# pc-gen-usb-fixgain.net
KiCad netlist of a schematic drawn in EAGLE
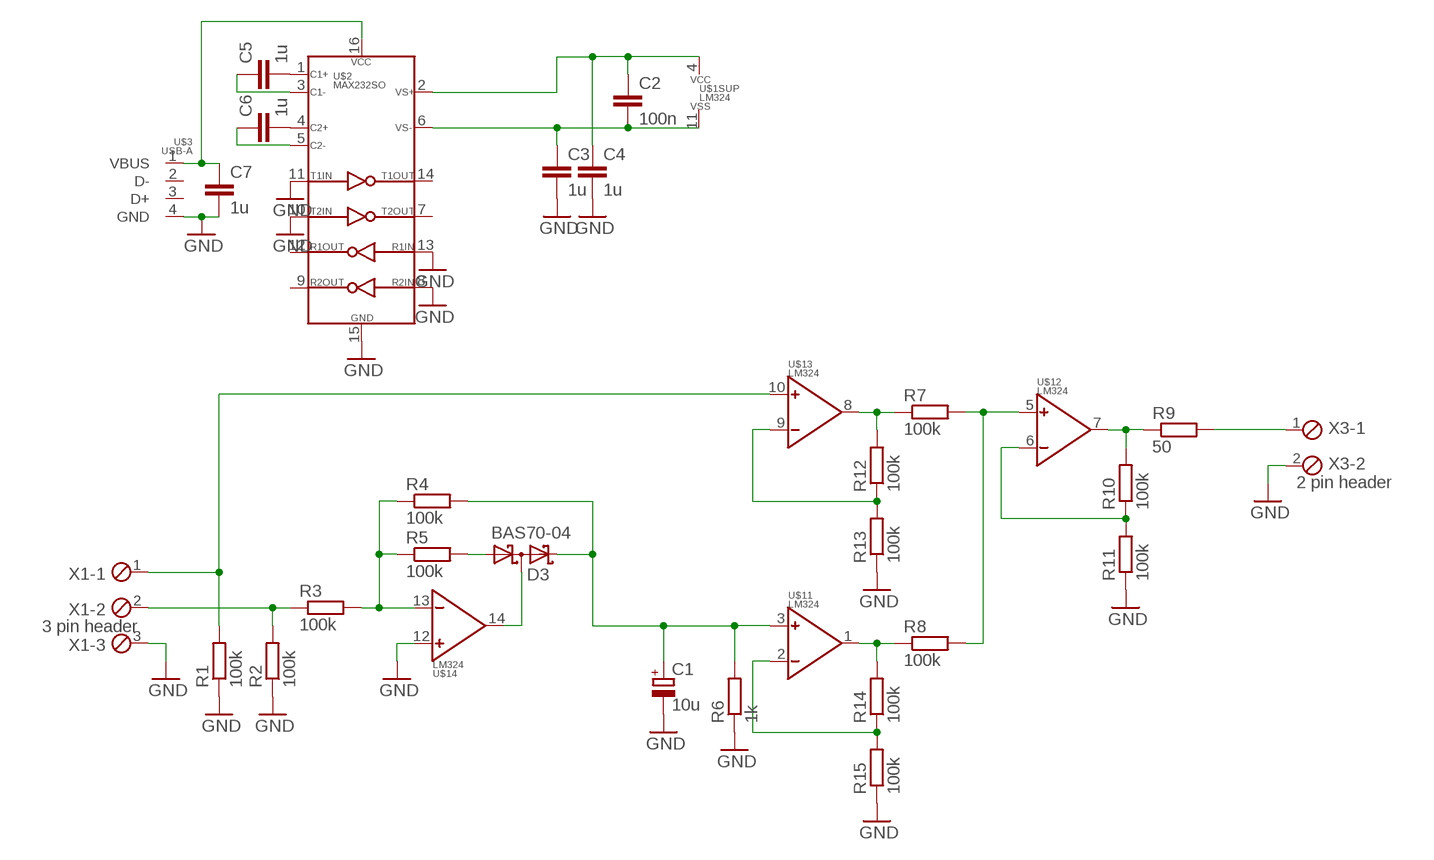
[diagram p0: schematic, sheet 1]

(export (version "E")
  (design (tool "Eeschema 10.0.6"))
  (components
    (comp (ref "C1")
      (value "10u")
      (footprint "eagle-import:E2,5-7")
      (libsource (lib "eagle-import") (part "CPOL-EUE2.5-7"))
    )
    (comp (ref "C2")
      (value "100n")
      (footprint "eagle-import:C1206")
      (libsource (lib "eagle-import") (part "C-EUC1206"))
    )
    (comp (ref "C3")
      (value "1u")
      (footprint "eagle-import:C1206")
      (libsource (lib "eagle-import") (part "C-EUC1206"))
    )
    (comp (ref "C4")
      (value "1u")
      (footprint "eagle-import:C1206")
      (libsource (lib "eagle-import") (part "C-EUC1206"))
    )
    (comp (ref "C5")
      (value "1u")
      (footprint "eagle-import:C1206")
      (libsource (lib "eagle-import") (part "C-EUC1206"))
    )
    (comp (ref "C6")
      (value "1u")
      (footprint "eagle-import:C1206")
      (libsource (lib "eagle-import") (part "C-EUC1206"))
    )
    (comp (ref "C7")
      (value "1u")
      (footprint "eagle-import:C1206")
      (libsource (lib "eagle-import") (part "C-EUC1206"))
    )
    (comp (ref "D3")
      (value "BAS70-04")
      (footprint "eagle-import:SOT23")
      (libsource (lib "eagle-import") (part "BAS70-04"))
    )
    (comp (ref "R1")
      (value "100k")
      (footprint "eagle-import:R1206")
      (libsource (lib "eagle-import") (part "R-EU_R1206"))
    )
    (comp (ref "R2")
      (value "100k")
      (footprint "eagle-import:R1206")
      (libsource (lib "eagle-import") (part "R-EU_R1206"))
    )
    (comp (ref "R3")
      (value "100k")
      (footprint "eagle-import:R1206")
      (libsource (lib "eagle-import") (part "R-EU_R1206"))
    )
    (comp (ref "R4")
      (value "100k")
      (footprint "eagle-import:R1206")
      (libsource (lib "eagle-import") (part "R-EU_R1206"))
    )
    (comp (ref "R5")
      (value "100k")
      (footprint "eagle-import:R1206")
      (libsource (lib "eagle-import") (part "R-EU_R1206"))
    )
    (comp (ref "R6")
      (value "1k")
      (footprint "eagle-import:R1206")
      (libsource (lib "eagle-import") (part "R-EU_R1206"))
    )
    (comp (ref "R7")
      (value "100k")
      (footprint "eagle-import:R1206")
      (libsource (lib "eagle-import") (part "R-EU_R1206"))
    )
    (comp (ref "R8")
      (value "100k")
      (footprint "eagle-import:R1206")
      (libsource (lib "eagle-import") (part "R-EU_R1206"))
    )
    (comp (ref "R9")
      (value "50")
      (footprint "eagle-import:R1206")
      (libsource (lib "eagle-import") (part "R-EU_R1206"))
    )
    (comp (ref "R10")
      (value "100k")
      (footprint "eagle-import:R1206")
      (libsource (lib "eagle-import") (part "R-EU_R1206"))
    )
    (comp (ref "R11")
      (value "100k")
      (footprint "eagle-import:R1206")
      (libsource (lib "eagle-import") (part "R-EU_R1206"))
    )
    (comp (ref "R12")
      (value "100k")
      (footprint "eagle-import:R1206")
      (libsource (lib "eagle-import") (part "R-EU_R1206"))
    )
    (comp (ref "R13")
      (value "100k")
      (footprint "eagle-import:R1206")
      (libsource (lib "eagle-import") (part "R-EU_R1206"))
    )
    (comp (ref "R14")
      (value "100k")
      (footprint "eagle-import:R1206")
      (libsource (lib "eagle-import") (part "R-EU_R1206"))
    )
    (comp (ref "R15")
      (value "100k")
      (footprint "eagle-import:R1206")
      (libsource (lib "eagle-import") (part "R-EU_R1206"))
    )
    (comp (ref "U$1")
      (value "LM324")
      (footprint "eagle-import:SO14")
      (libsource (lib "eagle-import") (part "OP-QUADSO14"))
    )
    (comp (ref "U$2")
      (value "MAX232SO")
      (footprint "eagle-import:SO16")
      (libsource (lib "eagle-import") (part "MAX232SO"))
    )
    (comp (ref "U$3")
      (value "USB-A")
      (footprint "eagle-import:USB-A")
      (libsource (lib "eagle-import") (part "USB-A"))
    )
    (comp (ref "X1")
      (value "3 pin header")
      (footprint "eagle-import:3POL254")
      (libsource (lib "eagle-import") (part "MPT3"))
    )
    (comp (ref "X3")
      (value "2 pin header")
      (footprint "eagle-import:2POL254")
      (libsource (lib "eagle-import") (part "MPT2"))
    )
  )
  (nets
    (net (code "1") (name "GND") (class "Default")
      (node (ref "C1") (pin "-") (pinfunction "-_-") (pintype "passive"))
      (node (ref "C3") (pin "2") (pinfunction "2_2") (pintype "passive"))
      (node (ref "C4") (pin "2") (pinfunction "2_2") (pintype "passive"))
      (node (ref "C7") (pin "2") (pinfunction "2_2") (pintype "passive"))
      (node (ref "R1") (pin "1") (pinfunction "1_1") (pintype "passive"))
      (node (ref "R11") (pin "1") (pinfunction "1_1") (pintype "passive"))
      (node (ref "R13") (pin "1") (pinfunction "1_1") (pintype "passive"))
      (node (ref "R15") (pin "1") (pinfunction "1_1") (pintype "passive"))
      (node (ref "R2") (pin "1") (pinfunction "1_1") (pintype "passive"))
      (node (ref "R6") (pin "1") (pinfunction "1_1") (pintype "passive"))
      (node (ref "U$1") (pin "12") (pinfunction "POS_12") (pintype "bidirectional"))
      (node (ref "U$2") (pin "10") (pinfunction "T2IN_10") (pintype "bidirectional"))
      (node (ref "U$2") (pin "11") (pinfunction "T1IN_11") (pintype "bidirectional"))
      (node (ref "U$2") (pin "13") (pinfunction "R1IN_13") (pintype "bidirectional"))
      (node (ref "U$2") (pin "15") (pinfunction "GND_15") (pintype "bidirectional"))
      (node (ref "U$2") (pin "8") (pinfunction "R2IN_8") (pintype "bidirectional"))
      (node (ref "U$3") (pin "4") (pinfunction "GND_4") (pintype "bidirectional"))
      (node (ref "X1") (pin "3") (pinfunction "1_3") (pintype "passive"))
      (node (ref "X3") (pin "2") (pinfunction "1_2") (pintype "passive"))
    )
    (net (code "2") (name "Net-(D3-A1)") (class "Default")
      (node (ref "D3") (pin "1") (pinfunction "A1_1") (pintype "passive"))
      (node (ref "R5") (pin "2") (pinfunction "2_2") (pintype "passive"))
    )
    (net (code "3") (name "Net-(D3-C1A2)") (class "Default")
      (node (ref "D3") (pin "3") (pinfunction "C1A2_3") (pintype "passive"))
      (node (ref "U$1") (pin "14") (pinfunction "OUT_14") (pintype "bidirectional"))
    )
    (net (code "4") (name "Net-(D3-C2)") (class "Default")
      (node (ref "C1") (pin "+") (pinfunction "+_+") (pintype "passive"))
      (node (ref "D3") (pin "2") (pinfunction "C2_2") (pintype "passive"))
      (node (ref "R4") (pin "2") (pinfunction "2_2") (pintype "passive"))
      (node (ref "R6") (pin "2") (pinfunction "2_2") (pintype "passive"))
      (node (ref "U$1") (pin "3") (pinfunction "POS_3") (pintype "bidirectional"))
    )
    (net (code "5") (name "Net-(R9-Pad2)") (class "Default")
      (node (ref "R9") (pin "2") (pinfunction "2_2") (pintype "passive"))
      (node (ref "X3") (pin "1") (pinfunction "1_1") (pintype "passive"))
    )
    (net (code "6") (name "Net-(U$1A-NEG)") (class "Default")
      (node (ref "R14") (pin "1") (pinfunction "1_1") (pintype "passive"))
      (node (ref "R15") (pin "2") (pinfunction "2_2") (pintype "passive"))
      (node (ref "U$1") (pin "2") (pinfunction "NEG_2") (pintype "bidirectional"))
    )
    (net (code "7") (name "Net-(U$1A-OUT)") (class "Default")
      (node (ref "R14") (pin "2") (pinfunction "2_2") (pintype "passive"))
      (node (ref "R8") (pin "1") (pinfunction "1_1") (pintype "passive"))
      (node (ref "U$1") (pin "1") (pinfunction "OUT_1") (pintype "bidirectional"))
    )
    (net (code "8") (name "Net-(U$1B-NEG)") (class "Default")
      (node (ref "R10") (pin "1") (pinfunction "1_1") (pintype "passive"))
      (node (ref "R11") (pin "2") (pinfunction "2_2") (pintype "passive"))
      (node (ref "U$1") (pin "6") (pinfunction "NEG_6") (pintype "bidirectional"))
    )
    (net (code "9") (name "Net-(U$1B-OUT)") (class "Default")
      (node (ref "R10") (pin "2") (pinfunction "2_2") (pintype "passive"))
      (node (ref "R9") (pin "1") (pinfunction "1_1") (pintype "passive"))
      (node (ref "U$1") (pin "7") (pinfunction "OUT_7") (pintype "bidirectional"))
    )
    (net (code "10") (name "Net-(U$1B-POS)") (class "Default")
      (node (ref "R7") (pin "2") (pinfunction "2_2") (pintype "passive"))
      (node (ref "R8") (pin "2") (pinfunction "2_2") (pintype "passive"))
      (node (ref "U$1") (pin "5") (pinfunction "POS_5") (pintype "bidirectional"))
    )
    (net (code "11") (name "Net-(U$1C-NEG)") (class "Default")
      (node (ref "R12") (pin "1") (pinfunction "1_1") (pintype "passive"))
      (node (ref "R13") (pin "2") (pinfunction "2_2") (pintype "passive"))
      (node (ref "U$1") (pin "9") (pinfunction "NEG_9") (pintype "bidirectional"))
    )
    (net (code "12") (name "Net-(U$1C-OUT)") (class "Default")
      (node (ref "R12") (pin "2") (pinfunction "2_2") (pintype "passive"))
      (node (ref "R7") (pin "1") (pinfunction "1_1") (pintype "passive"))
      (node (ref "U$1") (pin "8") (pinfunction "OUT_8") (pintype "bidirectional"))
    )
    (net (code "13") (name "Net-(U$1C-POS)") (class "Default")
      (node (ref "R1") (pin "2") (pinfunction "2_2") (pintype "passive"))
      (node (ref "U$1") (pin "10") (pinfunction "POS_10") (pintype "bidirectional"))
      (node (ref "X1") (pin "1") (pinfunction "1_1") (pintype "passive"))
    )
    (net (code "14") (name "Net-(U$1D-NEG)") (class "Default")
      (node (ref "R3") (pin "2") (pinfunction "2_2") (pintype "passive"))
      (node (ref "R4") (pin "1") (pinfunction "1_1") (pintype "passive"))
      (node (ref "R5") (pin "1") (pinfunction "1_1") (pintype "passive"))
      (node (ref "U$1") (pin "13") (pinfunction "NEG_13") (pintype "bidirectional"))
    )
    (net (code "15") (name "Net-(U$1E-VCC)") (class "Default")
      (node (ref "C2") (pin "1") (pinfunction "1_1") (pintype "passive"))
      (node (ref "C4") (pin "1") (pinfunction "1_1") (pintype "passive"))
      (node (ref "U$1") (pin "4") (pinfunction "VCC_4") (pintype "bidirectional"))
      (node (ref "U$2") (pin "2") (pinfunction "VS+_2") (pintype "bidirectional"))
    )
    (net (code "16") (name "Net-(U$1E-VSS)") (class "Default")
      (node (ref "C2") (pin "2") (pinfunction "2_2") (pintype "passive"))
      (node (ref "C3") (pin "1") (pinfunction "1_1") (pintype "passive"))
      (node (ref "U$1") (pin "11") (pinfunction "VSS_11") (pintype "bidirectional"))
      (node (ref "U$2") (pin "6") (pinfunction "VS-_6") (pintype "bidirectional"))
    )
    (net (code "17") (name "Net-(U$2-C1+)") (class "Default")
      (node (ref "C5") (pin "2") (pinfunction "2_2") (pintype "passive"))
      (node (ref "U$2") (pin "1") (pinfunction "C1+_1") (pintype "bidirectional"))
    )
    (net (code "18") (name "Net-(U$2-C1-)") (class "Default")
      (node (ref "C5") (pin "1") (pinfunction "1_1") (pintype "passive"))
      (node (ref "U$2") (pin "3") (pinfunction "C1-_3") (pintype "bidirectional"))
    )
    (net (code "19") (name "Net-(U$2-C2+)") (class "Default")
      (node (ref "C6") (pin "2") (pinfunction "2_2") (pintype "passive"))
      (node (ref "U$2") (pin "4") (pinfunction "C2+_4") (pintype "bidirectional"))
    )
    (net (code "20") (name "Net-(U$2-C2-)") (class "Default")
      (node (ref "C6") (pin "1") (pinfunction "1_1") (pintype "passive"))
      (node (ref "U$2") (pin "5") (pinfunction "C2-_5") (pintype "bidirectional"))
    )
    (net (code "21") (name "Net-(U$2-VCC)") (class "Default")
      (node (ref "C7") (pin "1") (pinfunction "1_1") (pintype "passive"))
      (node (ref "U$2") (pin "16") (pinfunction "VCC_16") (pintype "bidirectional"))
      (node (ref "U$3") (pin "1") (pinfunction "VBUS_1") (pintype "bidirectional"))
    )
    (net (code "22") (name "Net-(X1B-1)") (class "Default")
      (node (ref "R2") (pin "2") (pinfunction "2_2") (pintype "passive"))
      (node (ref "R3") (pin "1") (pinfunction "1_1") (pintype "passive"))
      (node (ref "X1") (pin "2") (pinfunction "1_2") (pintype "passive"))
    )
    (net (code "23") (name "unconnected-(U$2-R1OUT-Pad12)") (class "Default")
      (node (ref "U$2") (pin "12") (pinfunction "R1OUT_12") (pintype "bidirectional"))
    )
    (net (code "24") (name "unconnected-(U$2-R2OUT-Pad9)") (class "Default")
      (node (ref "U$2") (pin "9") (pinfunction "R2OUT_9") (pintype "bidirectional"))
    )
    (net (code "25") (name "unconnected-(U$2-T1OUT-Pad14)") (class "Default")
      (node (ref "U$2") (pin "14") (pinfunction "T1OUT_14") (pintype "bidirectional"))
    )
    (net (code "26") (name "unconnected-(U$2-T2OUT-Pad7)") (class "Default")
      (node (ref "U$2") (pin "7") (pinfunction "T2OUT_7") (pintype "bidirectional"))
    )
    (net (code "27") (name "unconnected-(U$3-D+-Pad3)") (class "Default")
      (node (ref "U$3") (pin "3") (pinfunction "D+_3") (pintype "bidirectional"))
    )
    (net (code "28") (name "unconnected-(U$3-D--Pad2)") (class "Default")
      (node (ref "U$3") (pin "2") (pinfunction "D-_2") (pintype "bidirectional"))
    )
  )
)
